# Adafruit_LTC4311_I2C_Extender.net
KiCad netlist of a schematic drawn in EAGLE
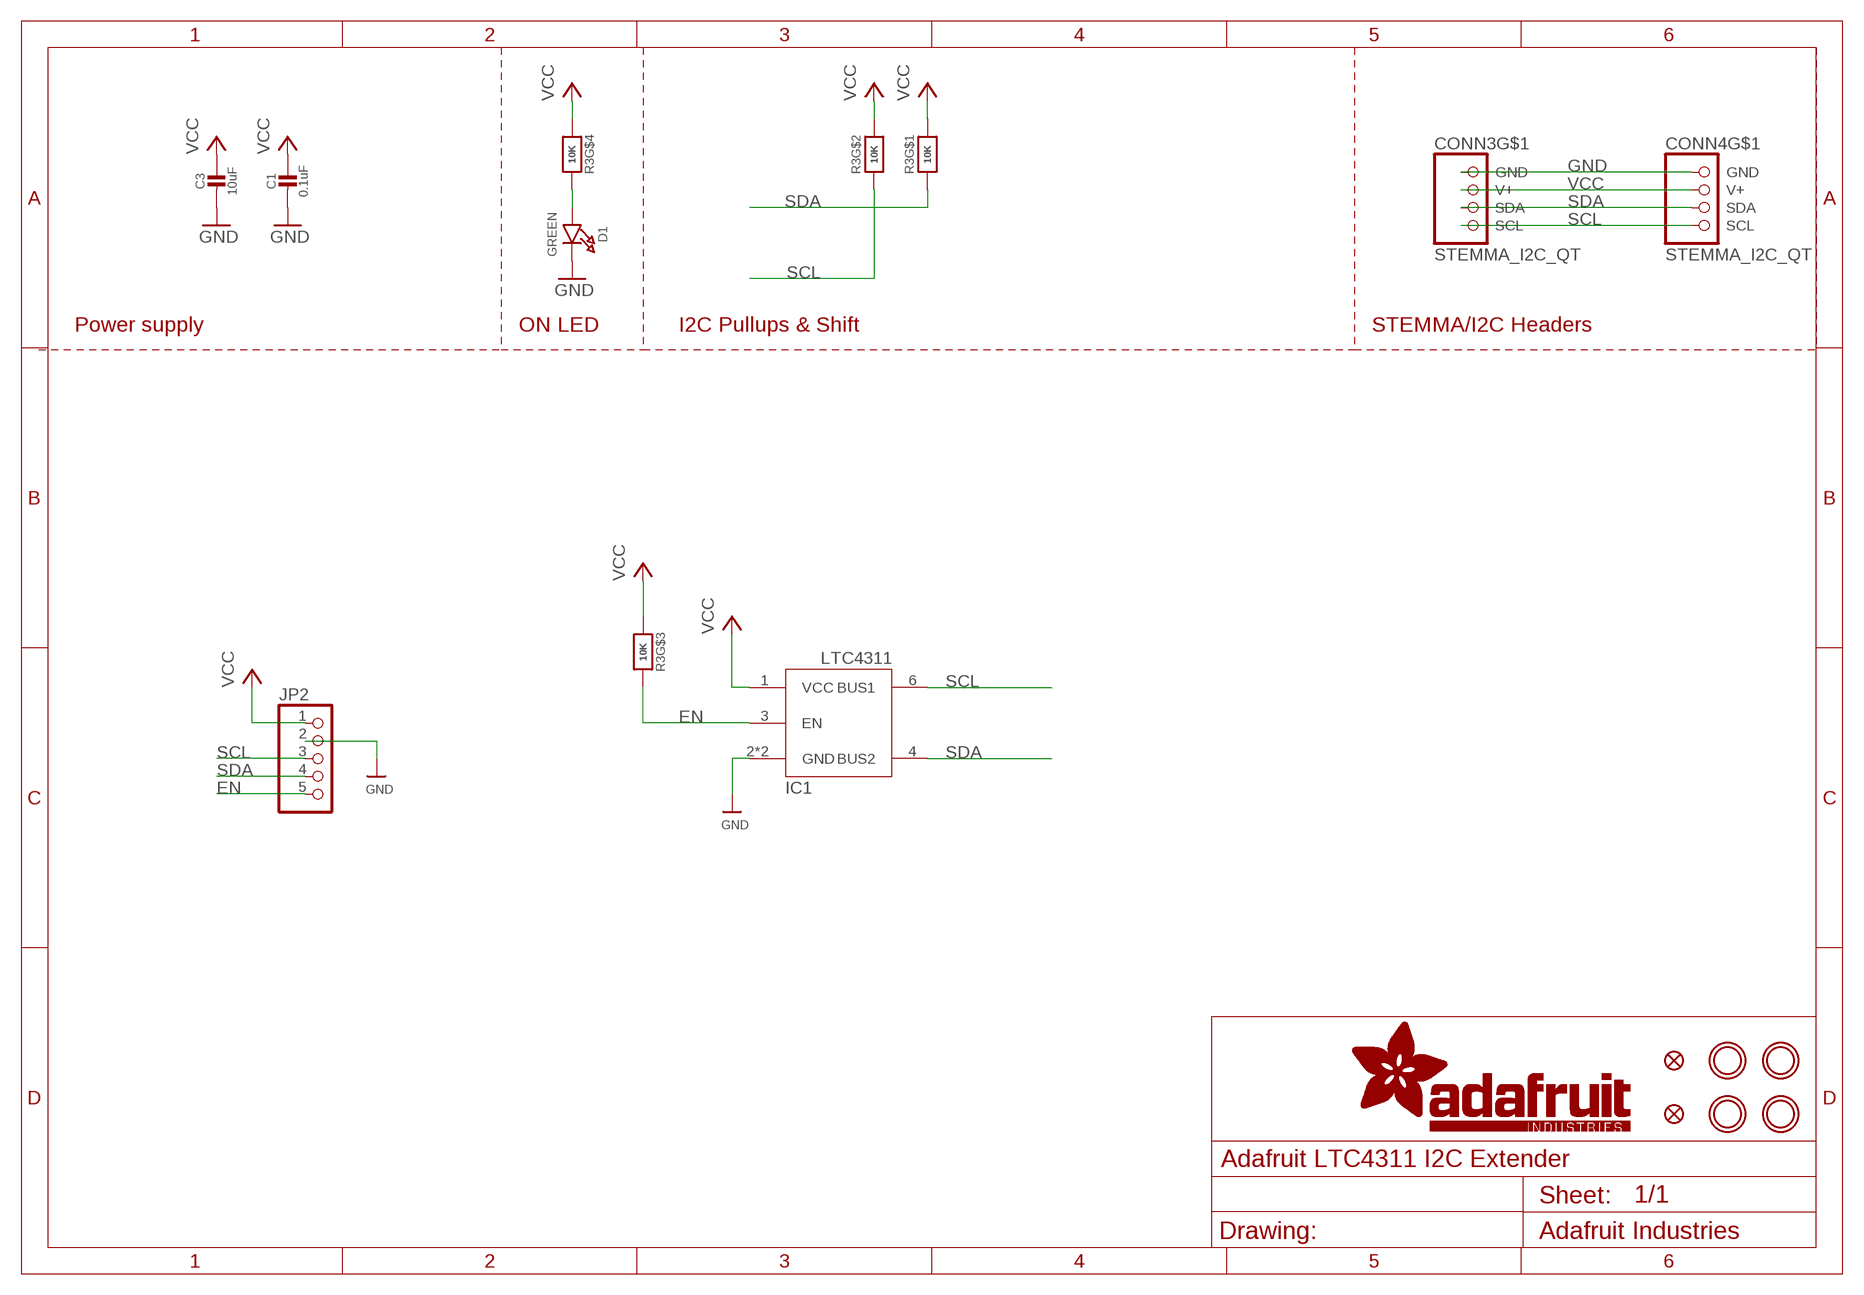
[diagram p0: schematic, sheet 1]

(export (version "E")
  (design (tool "Eeschema 10.0.6"))
  (components
    (comp (ref "C1")
      (value "0.1uF")
      (footprint "eagle-import:0603-NO")
      (libsource (lib "eagle-import") (part "CAP_CERAMIC0603_NO"))
    )
    (comp (ref "C3")
      (value "10uF")
      (footprint "eagle-import:0805-NO")
      (libsource (lib "eagle-import") (part "CAP_CERAMIC0805-NOOUTLINE"))
    )
    (comp (ref "CONN3")
      (value "STEMMA_I2C_QT")
      (footprint "eagle-import:JST_SH4")
      (libsource (lib "eagle-import") (part "STEMMA_I2C_QT"))
    )
    (comp (ref "CONN4")
      (value "STEMMA_I2C_QT")
      (footprint "eagle-import:JST_SH4")
      (libsource (lib "eagle-import") (part "STEMMA_I2C_QT"))
    )
    (comp (ref "D1")
      (value "GREEN")
      (footprint "eagle-import:CHIPLED_0603_NOOUTLINE")
      (libsource (lib "eagle-import") (part "LED0603_NOOUTLINE"))
    )
    (comp (ref "FID3")
      (value "FIDUCIAL_1MM")
      (footprint "eagle-import:FIDUCIAL_1MM")
      (libsource (lib "eagle-import") (part "FIDUCIAL_1MM"))
    )
    (comp (ref "FID4")
      (value "FIDUCIAL_1MM")
      (footprint "eagle-import:FIDUCIAL_1MM")
      (libsource (lib "eagle-import") (part "FIDUCIAL_1MM"))
    )
    (comp (ref "IC1")
      (value "LTC4311_SC70")
      (footprint "eagle-import:SC70-6L")
      (libsource (lib "eagle-import") (part "LTC4311_SC70"))
    )
    (comp (ref "JP2")
      (value "HEADER-1X570MIL")
      (footprint "eagle-import:1X05_ROUND_70")
      (libsource (lib "eagle-import") (part "HEADER-1X570MIL"))
    )
    (comp (ref "R3")
      (value "10K")
      (footprint "eagle-import:RESPACK_4X0603")
      (libsource (lib "eagle-import") (part "RESISTOR_4PACK"))
    )
    (comp (ref "U$1")
      (value "MOUNTINGHOLE2.5")
      (footprint "eagle-import:MOUNTINGHOLE_2.5_PLATED")
      (libsource (lib "eagle-import") (part "MOUNTINGHOLE2.5"))
    )
    (comp (ref "U$17")
      (value "MOUNTINGHOLE2.5")
      (footprint "eagle-import:MOUNTINGHOLE_2.5_PLATED")
      (libsource (lib "eagle-import") (part "MOUNTINGHOLE2.5"))
    )
    (comp (ref "U$19")
      (value "MOUNTINGHOLE2.5")
      (footprint "eagle-import:MOUNTINGHOLE_2.5_PLATED")
      (libsource (lib "eagle-import") (part "MOUNTINGHOLE2.5"))
    )
    (comp (ref "U$21")
      (value "MOUNTINGHOLE2.5")
      (footprint "eagle-import:MOUNTINGHOLE_2.5_PLATED")
      (libsource (lib "eagle-import") (part "MOUNTINGHOLE2.5"))
    )
  )
  (nets
    (net (code "1") (name "/EN") (class "Default")
      (node (ref "IC1") (pin "3") (pinfunction "EN_3") (pintype "input"))
      (node (ref "JP2") (pin "5") (pinfunction "5_5") (pintype "passive"))
      (node (ref "R3") (pin "6") (pinfunction "2_6") (pintype "passive"))
    )
    (net (code "2") (name "/SCL") (class "Default")
      (node (ref "CONN3") (pin "4") (pinfunction "SCL_4") (pintype "passive"))
      (node (ref "CONN4") (pin "4") (pinfunction "SCL_4") (pintype "passive"))
      (node (ref "IC1") (pin "6") (pinfunction "BUS1_6") (pintype "bidirectional"))
      (node (ref "JP2") (pin "3") (pinfunction "3_3") (pintype "passive"))
      (node (ref "R3") (pin "2") (pinfunction "1_2") (pintype "passive"))
    )
    (net (code "3") (name "/SDA") (class "Default")
      (node (ref "CONN3") (pin "3") (pinfunction "SDA_3") (pintype "passive"))
      (node (ref "CONN4") (pin "3") (pinfunction "SDA_3") (pintype "passive"))
      (node (ref "IC1") (pin "4") (pinfunction "BUS2_4") (pintype "bidirectional"))
      (node (ref "JP2") (pin "4") (pinfunction "4_4") (pintype "passive"))
      (node (ref "R3") (pin "1") (pinfunction "1_1") (pintype "passive"))
    )
    (net (code "4") (name "GND") (class "Default")
      (node (ref "C1") (pin "2") (pinfunction "2_2") (pintype "passive"))
      (node (ref "C3") (pin "2") (pinfunction "2_2") (pintype "passive"))
      (node (ref "CONN3") (pin "1") (pinfunction "GND_1") (pintype "passive"))
      (node (ref "CONN4") (pin "1") (pinfunction "GND_1") (pintype "passive"))
      (node (ref "D1") (pin "C") (pinfunction "C_C") (pintype "passive"))
      (node (ref "IC1") (pin "2") (pinfunction "GND_2") (pintype "power_in"))
      (node (ref "IC1") (pin "5") (pinfunction "GND_5") (pintype "power_in"))
      (node (ref "JP2") (pin "2") (pinfunction "2_2") (pintype "passive"))
    )
    (net (code "5") (name "Net-(R3D-2)") (class "Default")
      (node (ref "D1") (pin "A") (pinfunction "A_A") (pintype "passive"))
      (node (ref "R3") (pin "5") (pinfunction "2_5") (pintype "passive"))
    )
    (net (code "6") (name "VCC") (class "Default")
      (node (ref "C1") (pin "1") (pinfunction "1_1") (pintype "passive"))
      (node (ref "C3") (pin "1") (pinfunction "1_1") (pintype "passive"))
      (node (ref "CONN3") (pin "2") (pinfunction "V+_2") (pintype "passive"))
      (node (ref "CONN4") (pin "2") (pinfunction "V+_2") (pintype "passive"))
      (node (ref "IC1") (pin "1") (pinfunction "VCC_1") (pintype "power_in"))
      (node (ref "JP2") (pin "1") (pinfunction "1_1") (pintype "passive"))
      (node (ref "R3") (pin "3") (pinfunction "1_3") (pintype "passive"))
      (node (ref "R3") (pin "4") (pinfunction "1_4") (pintype "passive"))
      (node (ref "R3") (pin "7") (pinfunction "2_7") (pintype "passive"))
      (node (ref "R3") (pin "8") (pinfunction "2_8") (pintype "passive"))
    )
  )
)
